# EFNMR_RT_V1.net
KiCad netlist of a schematic drawn in Altium Designer
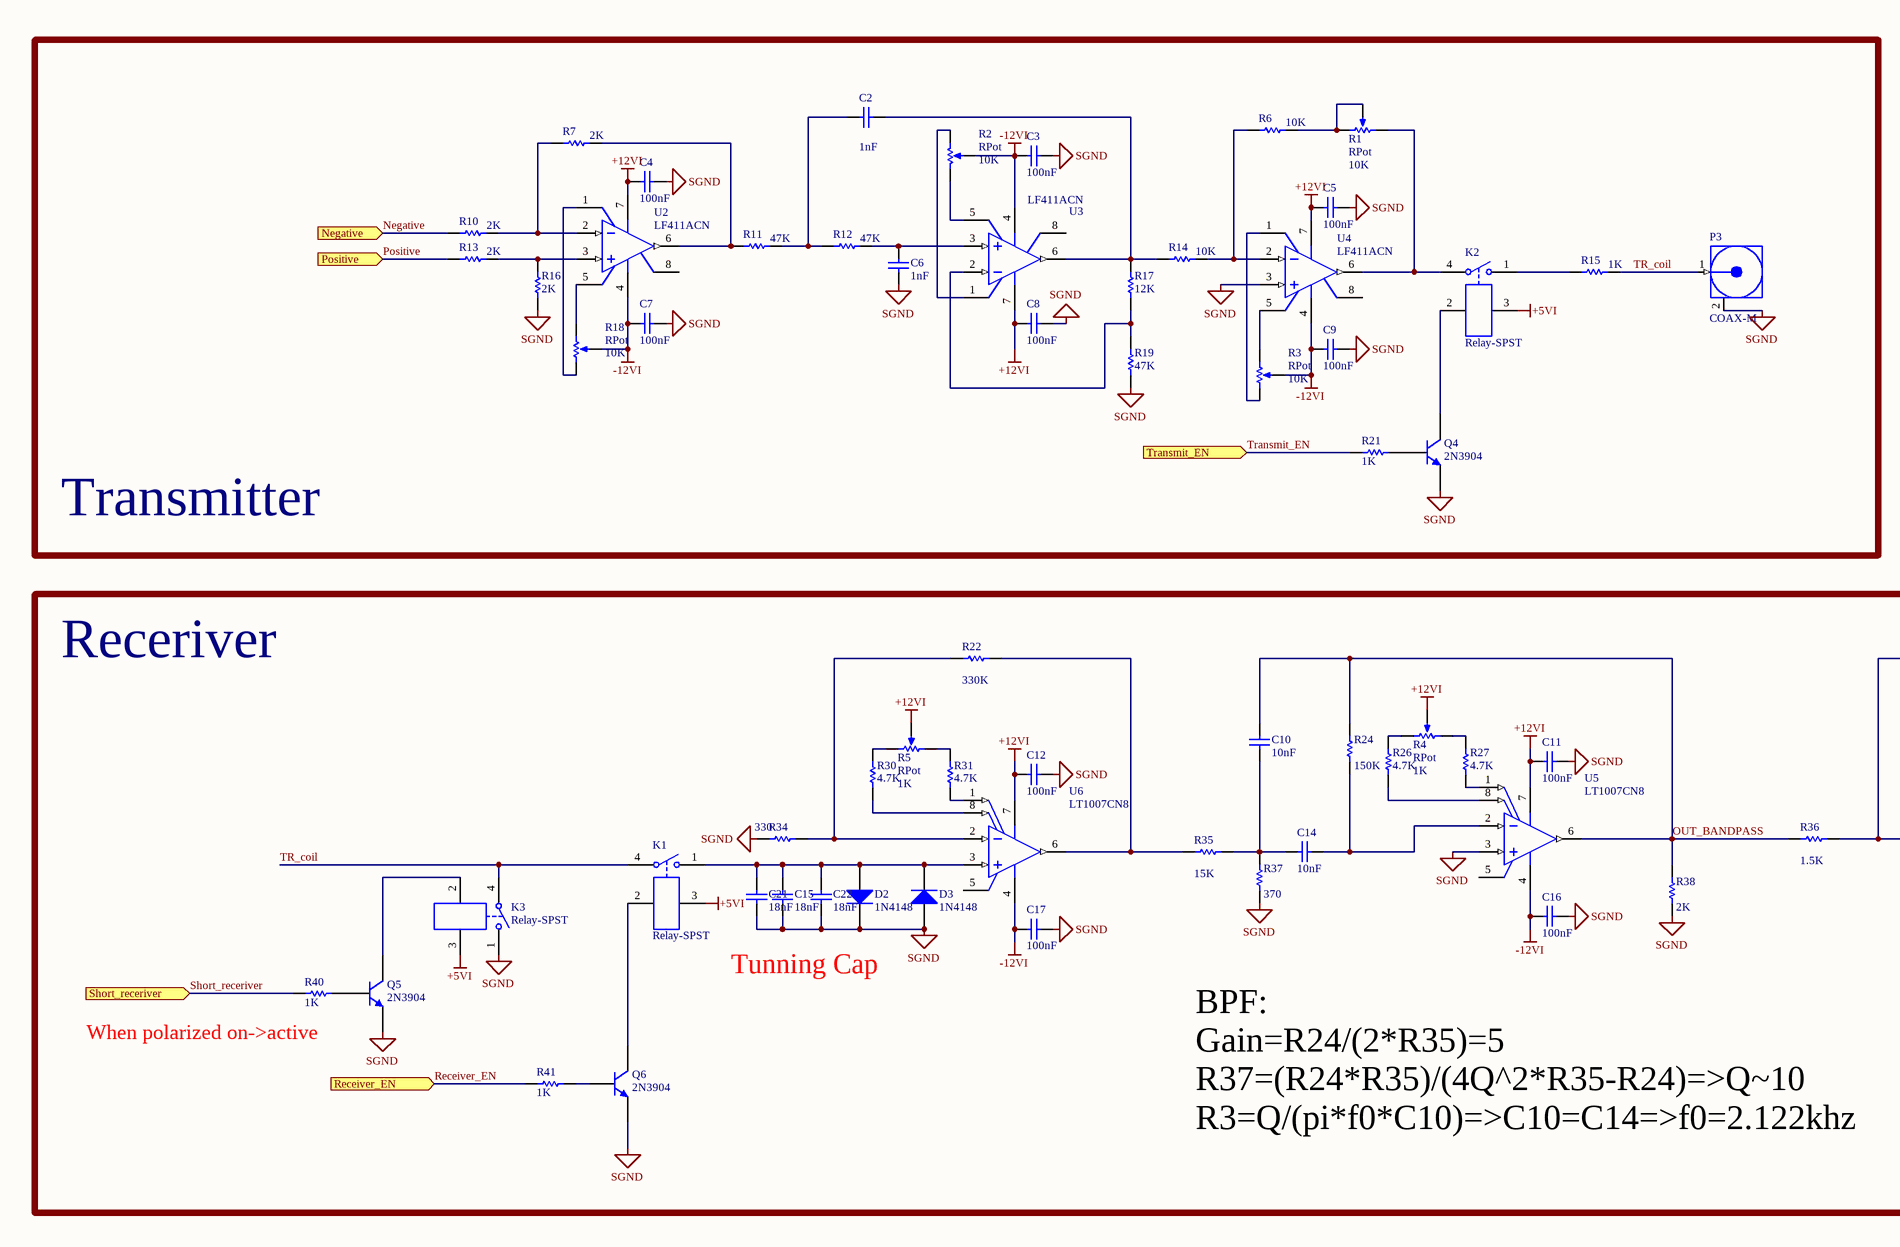
[diagram p0: EFNMR_RT_V1.SchDoc, left]
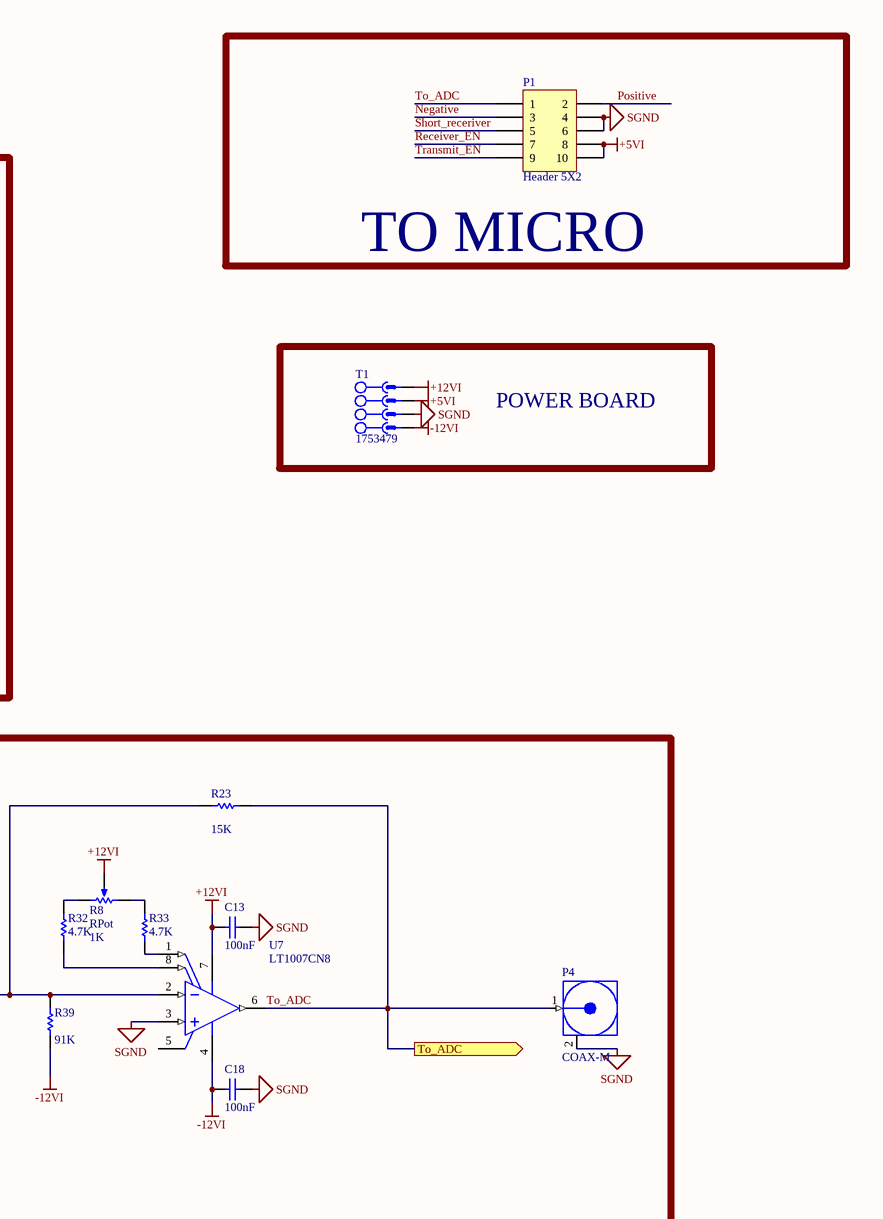
[diagram p1: EFNMR_RT_V1.SchDoc, right]

(export (version "E")
  (design (tool "Eeschema 10.0.6"))
  (components
    (comp (ref "C2")
      (value "1nF")
      (footprint "CAP0805")
      (description "Capacitor")
      (fields (field (name "Comment") "Cap") (field (name "PUBLISHER") "Altium Limited"))
      (libsource (lib "Miscellaneous Devices") (part "Cap"))
    )
    (comp (ref "C3")
      (value "100nF")
      (footprint "CAP0805")
      (description "Capacitor")
      (fields (field (name "Comment") "Cap") (field (name "PUBLISHER") "Altium Limited"))
      (libsource (lib "Miscellaneous Devices") (part "Cap"))
    )
    (comp (ref "C4")
      (value "100nF")
      (footprint "CAP0805")
      (description "Capacitor")
      (fields (field (name "Comment") "Cap") (field (name "PUBLISHER") "Altium Limited"))
      (libsource (lib "Miscellaneous Devices") (part "Cap"))
    )
    (comp (ref "C5")
      (value "100nF")
      (footprint "CAP0805")
      (description "Capacitor")
      (fields (field (name "Comment") "Cap") (field (name "PUBLISHER") "Altium Limited"))
      (libsource (lib "Miscellaneous Devices") (part "Cap"))
    )
    (comp (ref "C6")
      (value "1nF")
      (footprint "CAP0805")
      (description "Capacitor")
      (fields (field (name "Comment") "Cap") (field (name "PUBLISHER") "Altium Limited"))
      (libsource (lib "Miscellaneous Devices") (part "Cap"))
    )
    (comp (ref "C7")
      (value "100nF")
      (footprint "CAP0805")
      (description "Capacitor")
      (fields (field (name "Comment") "Cap") (field (name "PUBLISHER") "Altium Limited"))
      (libsource (lib "Miscellaneous Devices") (part "Cap"))
    )
    (comp (ref "C8")
      (value "100nF")
      (footprint "CAP0805")
      (description "Capacitor")
      (fields (field (name "Comment") "Cap") (field (name "PUBLISHER") "Altium Limited"))
      (libsource (lib "Miscellaneous Devices") (part "Cap"))
    )
    (comp (ref "C9")
      (value "100nF")
      (footprint "CAP0805")
      (description "Capacitor")
      (fields (field (name "Comment") "Cap") (field (name "PUBLISHER") "Altium Limited"))
      (libsource (lib "Miscellaneous Devices") (part "Cap"))
    )
    (comp (ref "C10")
      (value "10nF")
      (footprint "CAP0805")
      (description "Capacitor")
      (fields (field (name "PUBLISHER") "Altium Limited"))
      (libsource (lib "Miscellaneous Devices") (part "Cap"))
    )
    (comp (ref "C11")
      (value "100nF")
      (footprint "CAP0805")
      (description "Capacitor")
      (fields (field (name "Comment") "Cap") (field (name "PUBLISHER") "Altium Limited"))
      (libsource (lib "Miscellaneous Devices") (part "Cap"))
    )
    (comp (ref "C12")
      (value "100nF")
      (footprint "CAP0805")
      (description "Capacitor")
      (fields (field (name "Comment") "Cap") (field (name "PUBLISHER") "Altium Limited"))
      (libsource (lib "Miscellaneous Devices") (part "Cap"))
    )
    (comp (ref "C13")
      (value "100nF")
      (footprint "CAP0805")
      (description "Capacitor")
      (fields (field (name "Comment") "Cap") (field (name "PUBLISHER") "Altium Limited"))
      (libsource (lib "Miscellaneous Devices") (part "Cap"))
    )
    (comp (ref "C14")
      (value "10nF")
      (footprint "CAP0805")
      (description "Capacitor")
      (fields (field (name "PUBLISHER") "Altium Limited"))
      (libsource (lib "Miscellaneous Devices") (part "Cap"))
    )
    (comp (ref "C15")
      (value "18nF")
      (footprint "CAP0805")
      (description "Capacitor")
      (fields (field (name "Comment") "Cap") (field (name "PUBLISHER") "Altium Limited"))
      (libsource (lib "Miscellaneous Devices") (part "Cap"))
    )
    (comp (ref "C16")
      (value "100nF")
      (footprint "CAP0805")
      (description "Capacitor")
      (fields (field (name "Comment") "Cap") (field (name "PUBLISHER") "Altium Limited"))
      (libsource (lib "Miscellaneous Devices") (part "Cap"))
    )
    (comp (ref "C17")
      (value "100nF")
      (footprint "CAP0805")
      (description "Capacitor")
      (fields (field (name "Comment") "Cap") (field (name "PUBLISHER") "Altium Limited"))
      (libsource (lib "Miscellaneous Devices") (part "Cap"))
    )
    (comp (ref "C18")
      (value "100nF")
      (footprint "CAP0805")
      (description "Capacitor")
      (fields (field (name "Comment") "Cap") (field (name "PUBLISHER") "Altium Limited"))
      (libsource (lib "Miscellaneous Devices") (part "Cap"))
    )
    (comp (ref "C21")
      (value "18nF")
      (footprint "CAP0805")
      (description "Capacitor")
      (fields (field (name "Comment") "Cap") (field (name "PUBLISHER") "Altium Limited"))
      (libsource (lib "Miscellaneous Devices") (part "Cap"))
    )
    (comp (ref "C22")
      (value "18nF")
      (footprint "CAP0805")
      (description "Capacitor")
      (fields (field (name "Comment") "Cap") (field (name "PUBLISHER") "Altium Limited"))
      (libsource (lib "Miscellaneous Devices") (part "Cap"))
    )
    (comp (ref "D2")
      (value "1N4148")
      (footprint "SOD80, LL-34")
      (description "High Conductance Fast Diode")
      (fields (field (name "PUBLISHER") "Altium Limited"))
      (libsource (lib "FSC Discrete Diode") (part "1N4148"))
    )
    (comp (ref "D3")
      (value "1N4148")
      (footprint "SOD80, LL-34")
      (description "High Conductance Fast Diode")
      (fields (field (name "PUBLISHER") "Altium Limited"))
      (libsource (lib "FSC Discrete Diode") (part "1N4148"))
    )
    (comp (ref "K1")
      (value "Relay-SPST")
      (footprint "HE3351A0500")
      (description "Single-Pole Single-Throw Relay")
      (fields (field (name "PUBLISHER") "Altium Limited"))
      (libsource (lib "Miscellaneous Devices") (part "Relay-SPST"))
    )
    (comp (ref "K2")
      (value "Relay-SPST")
      (footprint "HE3351A0500")
      (description "Single-Pole Single-Throw Relay")
      (fields (field (name "PUBLISHER") "Altium Limited"))
      (libsource (lib "Miscellaneous Devices") (part "Relay-SPST"))
    )
    (comp (ref "K3")
      (value "Relay-SPST")
      (footprint "HE3351A0500")
      (description "Single-Pole Single-Throw Relay")
      (fields (field (name "PUBLISHER") "Altium Limited"))
      (libsource (lib "Miscellaneous Devices") (part "Relay-SPST"))
    )
    (comp (ref "P1")
      (value "Header 5X2")
      (footprint "IDC2.54-10PIN WITH CABLE")
      (description "Header, 5-Pin, Dual row")
      (fields (field (name "PUBLISHER") "Altium Limited"))
      (libsource (lib "Miscellaneous Connectors") (part "Header 5X2"))
    )
    (comp (ref "P3")
      (value "COAX-M")
      (footprint "SMA_RA_F")
      (description "RF Coaxial PCB Connector, MMCX; Thru-Hole, Vertical Mount Plug,  50 Ohm Impedance")
      (fields (field (name "PUBLISHER") "Altium Limited"))
      (libsource (lib "Miscellaneous Connectors") (part "COAX-M"))
    )
    (comp (ref "P4")
      (value "COAX-M")
      (footprint "SMA_RA_F")
      (description "RF Coaxial PCB Connector, MMCX; Thru-Hole, Vertical Mount Plug,  50 Ohm Impedance")
      (fields (field (name "PUBLISHER") "Altium Limited"))
      (libsource (lib "Miscellaneous Connectors") (part "COAX-M"))
    )
    (comp (ref "Q4")
      (value "2N3904")
      (footprint "TO-92A")
      (description "NPN General Purpose Amplifier")
      (fields (field (name "PUBLISHER") "Altium Limited"))
      (libsource (lib "Miscellaneous Devices") (part "2N3904"))
    )
    (comp (ref "Q5")
      (value "2N3904")
      (footprint "TO-92A")
      (description "NPN General Purpose Amplifier")
      (fields (field (name "PUBLISHER") "Altium Limited"))
      (libsource (lib "Miscellaneous Devices") (part "2N3904"))
    )
    (comp (ref "Q6")
      (value "2N3904")
      (footprint "TO-92A")
      (description "NPN General Purpose Amplifier")
      (fields (field (name "PUBLISHER") "Altium Limited"))
      (libsource (lib "Miscellaneous Devices") (part "2N3904"))
    )
    (comp (ref "R1")
      (value "RPot")
      (footprint "MULTITURN_TRIMMER_3296_132")
      (description "Potentiometer")
      (fields (field (name "ALTIUM_VALUE") "10K") (field (name "PUBLISHER") "Altium Limited"))
      (libsource (lib "Miscellaneous Devices") (part "RPot"))
    )
    (comp (ref "R2")
      (value "RPot")
      (footprint "MULTITURN_TRIMMER_3296_132")
      (description "Potentiometer")
      (fields (field (name "ALTIUM_VALUE") "10K") (field (name "PUBLISHER") "Altium Limited"))
      (libsource (lib "Miscellaneous Devices") (part "RPot"))
    )
    (comp (ref "R3")
      (value "RPot")
      (footprint "MULTITURN_TRIMMER_3296_132")
      (description "Potentiometer")
      (fields (field (name "ALTIUM_VALUE") "10K") (field (name "PUBLISHER") "Altium Limited"))
      (libsource (lib "Miscellaneous Devices") (part "RPot"))
    )
    (comp (ref "R4")
      (value "RPot")
      (footprint "MULTITURN_TRIMMER_3296_132")
      (description "Potentiometer")
      (fields (field (name "ALTIUM_VALUE") "1K") (field (name "PUBLISHER") "Altium Limited"))
      (libsource (lib "Miscellaneous Devices") (part "RPot"))
    )
    (comp (ref "R5")
      (value "RPot")
      (footprint "MULTITURN_TRIMMER_3296_132")
      (description "Potentiometer")
      (fields (field (name "ALTIUM_VALUE") "1K") (field (name "PUBLISHER") "Altium Limited"))
      (libsource (lib "Miscellaneous Devices") (part "RPot"))
    )
    (comp (ref "R6")
      (value "10K")
      (footprint "RES0805")
      (description "Resistor")
      (fields (field (name "PUBLISHER") "Altium Limited"))
      (libsource (lib "Miscellaneous Devices") (part "Res1"))
    )
    (comp (ref "R7")
      (value "2K")
      (footprint "RES0805")
      (description "Resistor")
      (fields (field (name "PUBLISHER") "Altium Limited"))
      (libsource (lib "Miscellaneous Devices") (part "Res1"))
    )
    (comp (ref "R8")
      (value "RPot")
      (footprint "MULTITURN_TRIMMER_3296_132")
      (description "Potentiometer")
      (fields (field (name "ALTIUM_VALUE") "1K") (field (name "PUBLISHER") "Altium Limited"))
      (libsource (lib "Miscellaneous Devices") (part "RPot"))
    )
    (comp (ref "R10")
      (value "2K")
      (footprint "RES0805")
      (description "Resistor")
      (fields (field (name "PUBLISHER") "Altium Limited"))
      (libsource (lib "Miscellaneous Devices") (part "Res1"))
    )
    (comp (ref "R11")
      (value "47K")
      (footprint "RES0805")
      (description "Resistor")
      (fields (field (name "PUBLISHER") "Altium Limited"))
      (libsource (lib "Miscellaneous Devices") (part "Res1"))
    )
    (comp (ref "R12")
      (value "47K")
      (footprint "RES0805")
      (description "Resistor")
      (fields (field (name "PUBLISHER") "Altium Limited"))
      (libsource (lib "Miscellaneous Devices") (part "Res1"))
    )
    (comp (ref "R13")
      (value "2K")
      (footprint "RES0805")
      (description "Resistor")
      (fields (field (name "PUBLISHER") "Altium Limited"))
      (libsource (lib "Miscellaneous Devices") (part "Res1"))
    )
    (comp (ref "R14")
      (value "10K")
      (footprint "RES0805")
      (description "Resistor")
      (fields (field (name "PUBLISHER") "Altium Limited"))
      (libsource (lib "Miscellaneous Devices") (part "Res1"))
    )
    (comp (ref "R15")
      (value "1K")
      (footprint "RES0805")
      (description "Resistor")
      (fields (field (name "PUBLISHER") "Altium Limited"))
      (libsource (lib "Miscellaneous Devices") (part "Res1"))
    )
    (comp (ref "R16")
      (value "2K")
      (footprint "RES0805")
      (description "Resistor")
      (fields (field (name "PUBLISHER") "Altium Limited"))
      (libsource (lib "Miscellaneous Devices") (part "Res1"))
    )
    (comp (ref "R17")
      (value "12K")
      (footprint "RES0805")
      (description "Resistor")
      (fields (field (name "PUBLISHER") "Altium Limited"))
      (libsource (lib "Miscellaneous Devices") (part "Res1"))
    )
    (comp (ref "R18")
      (value "RPot")
      (footprint "MULTITURN_TRIMMER_3296_132")
      (description "Potentiometer")
      (fields (field (name "ALTIUM_VALUE") "10K") (field (name "PUBLISHER") "Altium Limited"))
      (libsource (lib "Miscellaneous Devices") (part "RPot"))
    )
    (comp (ref "R19")
      (value "47K")
      (footprint "RES0805")
      (description "Resistor")
      (fields (field (name "PUBLISHER") "Altium Limited"))
      (libsource (lib "Miscellaneous Devices") (part "Res1"))
    )
    (comp (ref "R21")
      (value "1K")
      (footprint "RES0805")
      (description "Resistor")
      (fields (field (name "PUBLISHER") "Altium Limited"))
      (libsource (lib "Miscellaneous Devices") (part "Res1"))
    )
    (comp (ref "R22")
      (value "330K")
      (footprint "RES0805")
      (description "Resistor")
      (fields (field (name "PUBLISHER") "Altium Limited"))
      (libsource (lib "Miscellaneous Devices") (part "Res1"))
    )
    (comp (ref "R23")
      (value "15K")
      (footprint "RES0805")
      (description "Resistor")
      (fields (field (name "PUBLISHER") "Altium Limited"))
      (libsource (lib "Miscellaneous Devices") (part "Res1"))
    )
    (comp (ref "R24")
      (value "150K")
      (footprint "RES0805")
      (description "Resistor")
      (fields (field (name "PUBLISHER") "Altium Limited"))
      (libsource (lib "Miscellaneous Devices") (part "Res1"))
    )
    (comp (ref "R26")
      (value "4.7K")
      (footprint "RES0805")
      (description "Resistor")
      (fields (field (name "PUBLISHER") "Altium Limited"))
      (libsource (lib "Miscellaneous Devices") (part "Res1"))
    )
    (comp (ref "R27")
      (value "4.7K")
      (footprint "RES0805")
      (description "Resistor")
      (fields (field (name "PUBLISHER") "Altium Limited"))
      (libsource (lib "Miscellaneous Devices") (part "Res1"))
    )
    (comp (ref "R30")
      (value "4.7K")
      (footprint "RES0805")
      (description "Resistor")
      (fields (field (name "PUBLISHER") "Altium Limited"))
      (libsource (lib "Miscellaneous Devices") (part "Res1"))
    )
    (comp (ref "R31")
      (value "4.7K")
      (footprint "RES0805")
      (description "Resistor")
      (fields (field (name "PUBLISHER") "Altium Limited"))
      (libsource (lib "Miscellaneous Devices") (part "Res1"))
    )
    (comp (ref "R32")
      (value "4.7K")
      (footprint "RES0805")
      (description "Resistor")
      (fields (field (name "PUBLISHER") "Altium Limited"))
      (libsource (lib "Miscellaneous Devices") (part "Res1"))
    )
    (comp (ref "R33")
      (value "4.7K")
      (footprint "RES0805")
      (description "Resistor")
      (fields (field (name "PUBLISHER") "Altium Limited"))
      (libsource (lib "Miscellaneous Devices") (part "Res1"))
    )
    (comp (ref "R34")
      (value "330")
      (footprint "RES0805")
      (description "Resistor")
      (fields (field (name "PUBLISHER") "Altium Limited"))
      (libsource (lib "Miscellaneous Devices") (part "Res1"))
    )
    (comp (ref "R35")
      (value "15K")
      (footprint "RES0805")
      (description "Resistor")
      (fields (field (name "PUBLISHER") "Altium Limited"))
      (libsource (lib "Miscellaneous Devices") (part "Res1"))
    )
    (comp (ref "R36")
      (value "1.5K")
      (footprint "RES0805")
      (description "Resistor")
      (fields (field (name "PUBLISHER") "Altium Limited"))
      (libsource (lib "Miscellaneous Devices") (part "Res1"))
    )
    (comp (ref "R37")
      (value "370")
      (footprint "RES0805")
      (description "Resistor")
      (fields (field (name "PUBLISHER") "Altium Limited"))
      (libsource (lib "Miscellaneous Devices") (part "Res1"))
    )
    (comp (ref "R38")
      (value "2K")
      (footprint "RES0805")
      (description "Resistor")
      (fields (field (name "PUBLISHER") "Altium Limited"))
      (libsource (lib "Miscellaneous Devices") (part "Res1"))
    )
    (comp (ref "R39")
      (value "91K")
      (footprint "RES0805")
      (description "Resistor")
      (fields (field (name "PUBLISHER") "Altium Limited"))
      (libsource (lib "Miscellaneous Devices") (part "Res1"))
    )
    (comp (ref "R40")
      (value "1K")
      (footprint "RES0805")
      (description "Resistor")
      (fields (field (name "PUBLISHER") "Altium Limited"))
      (libsource (lib "Miscellaneous Devices") (part "Res1"))
    )
    (comp (ref "R41")
      (value "1K")
      (footprint "RES0805")
      (description "Resistor")
      (fields (field (name "PUBLISHER") "Altium Limited"))
      (libsource (lib "Miscellaneous Devices") (part "Res1"))
    )
    (comp (ref "T1")
      (value "1753479")
      (footprint "MSTBV 2,5/4-G-5")
      (description "4 Pitch: 5 mm Color: green Contact surface: Tin Assembly")
      (fields
        (field (name "MANUFACTURER") "PHOENIX CONTACT")
        (field (name "VOLTAGE") "320 V")
        (field (name "DESIGNER") "ABBAS BASEREH")
      )
      (libsource (lib "Mofidi3D") (part "CON_Phoenix_MSTBV_04"))
    )
    (comp (ref "U2")
      (value "LF411ACN")
      (footprint "LT-N8-8")
      (description "Low Offset, Low Drift JFET Input Operational Amplifier, 8-pin MDIP")
      (fields (field (name "MANUFACTURER") "National Semiconductor"))
      (libsource (lib "National Semiconductor Amplifier") (part "LF411ACN"))
    )
    (comp (ref "U3")
      (value "LF411ACN")
      (footprint "LT-N8-8")
      (description "Low Offset, Low Drift JFET Input Operational Amplifier, 8-pin MDIP")
      (fields (field (name "MANUFACTURER") "National Semiconductor"))
      (libsource (lib "National Semiconductor Amplifier") (part "LF411ACN"))
    )
    (comp (ref "U4")
      (value "LF411ACN")
      (footprint "LT-N8-8")
      (description "Low Offset, Low Drift JFET Input Operational Amplifier, 8-pin MDIP")
      (fields (field (name "MANUFACTURER") "National Semiconductor"))
      (libsource (lib "National Semiconductor Amplifier") (part "LF411ACN"))
    )
    (comp (ref "U5")
      (value "LT1007CN8")
      (footprint "LT-N8-8")
      (fields
        (field (name "LINEAR TECHNOLOGY PART NUMBER") "LT1007")
        (field (name "MANUFACTURER") "Linear Technology")
      )
      (libsource (lib "Linear Technology Operational Amplifiers (LT1000)") (part "LT1007CN8"))
    )
    (comp (ref "U6")
      (value "LT1007CN8")
      (footprint "LT-N8-8")
      (fields
        (field (name "LINEAR TECHNOLOGY PART NUMBER") "LT1007")
        (field (name "MANUFACTURER") "Linear Technology")
      )
      (libsource (lib "Linear Technology Operational Amplifiers (LT1000)") (part "LT1007CN8"))
    )
    (comp (ref "U7")
      (value "LT1007CN8")
      (footprint "LT-N8-8")
      (fields
        (field (name "LINEAR TECHNOLOGY PART NUMBER") "LT1007")
        (field (name "MANUFACTURER") "Linear Technology")
      )
      (libsource (lib "Linear Technology Operational Amplifiers (LT1000)") (part "LT1007CN8"))
    )
  )
  (nets
    (net (code "1") (name "+5VI") (class "Default")
      (node (ref "K1") (pin "3") (pinfunction "3_3") (pintype "passive"))
      (node (ref "K2") (pin "3") (pinfunction "3_3") (pintype "passive"))
      (node (ref "K3") (pin "3") (pinfunction "3_3") (pintype "passive"))
      (node (ref "P1") (pin "10") (pinfunction "10_10") (pintype "passive"))
      (node (ref "P1") (pin "8") (pinfunction "8_8") (pintype "passive"))
      (node (ref "T1") (pin "3") (pinfunction "3_3") (pintype "passive"))
    )
    (net (code "2") (name "+12VI") (class "Default")
      (node (ref "C11") (pin "2") (pinfunction "2_2") (pintype "passive"))
      (node (ref "C12") (pin "2") (pinfunction "2_2") (pintype "passive"))
      (node (ref "C13") (pin "2") (pinfunction "2_2") (pintype "passive"))
      (node (ref "C4") (pin "2") (pinfunction "2_2") (pintype "passive"))
      (node (ref "C5") (pin "2") (pinfunction "2_2") (pintype "passive"))
      (node (ref "C8") (pin "2") (pinfunction "2_2") (pintype "passive"))
      (node (ref "R4") (pin "3") (pinfunction "TAP_3") (pintype "passive"))
      (node (ref "R5") (pin "3") (pinfunction "TAP_3") (pintype "passive"))
      (node (ref "R8") (pin "3") (pinfunction "TAP_3") (pintype "passive"))
      (node (ref "T1") (pin "4") (pinfunction "4_4") (pintype "passive"))
      (node (ref "U2") (pin "7") (pinfunction "V+_7") (pintype "power_in"))
      (node (ref "U3") (pin "7") (pinfunction "V+_7") (pintype "power_in"))
      (node (ref "U4") (pin "7") (pinfunction "V+_7") (pintype "power_in"))
      (node (ref "U5") (pin "7") (pinfunction "V+_7") (pintype "power_in"))
      (node (ref "U6") (pin "7") (pinfunction "V+_7") (pintype "power_in"))
      (node (ref "U7") (pin "7") (pinfunction "V+_7") (pintype "power_in"))
    )
    (net (code "3") (name "-12VI") (class "Default")
      (node (ref "C16") (pin "2") (pinfunction "2_2") (pintype "passive"))
      (node (ref "C17") (pin "2") (pinfunction "2_2") (pintype "passive"))
      (node (ref "C18") (pin "2") (pinfunction "2_2") (pintype "passive"))
      (node (ref "C3") (pin "2") (pinfunction "2_2") (pintype "passive"))
      (node (ref "C7") (pin "2") (pinfunction "2_2") (pintype "passive"))
      (node (ref "C9") (pin "2") (pinfunction "2_2") (pintype "passive"))
      (node (ref "R18") (pin "3") (pinfunction "TAP_3") (pintype "passive"))
      (node (ref "R2") (pin "3") (pinfunction "TAP_3") (pintype "passive"))
      (node (ref "R3") (pin "3") (pinfunction "TAP_3") (pintype "passive"))
      (node (ref "R39") (pin "2") (pinfunction "2_2") (pintype "passive"))
      (node (ref "T1") (pin "1") (pinfunction "1_1") (pintype "passive"))
      (node (ref "U2") (pin "4") (pinfunction "V-_4") (pintype "power_in"))
      (node (ref "U3") (pin "4") (pinfunction "V-_4") (pintype "power_in"))
      (node (ref "U4") (pin "4") (pinfunction "V-_4") (pintype "power_in"))
      (node (ref "U5") (pin "4") (pinfunction "V-_4") (pintype "power_in"))
      (node (ref "U6") (pin "4") (pinfunction "V-_4") (pintype "power_in"))
      (node (ref "U7") (pin "4") (pinfunction "V-_4") (pintype "power_in"))
    )
    (net (code "4") (name "/Negative") (class "Default")
      (node (ref "P1") (pin "3") (pinfunction "3_3") (pintype "passive"))
      (node (ref "R10") (pin "1") (pinfunction "1_1") (pintype "passive"))
    )
    (net (code "5") (name "/OUT_BANDPASS") (class "Default")
      (node (ref "C10") (pin "2") (pinfunction "2_2") (pintype "passive"))
      (node (ref "R24") (pin "1") (pinfunction "1_1") (pintype "passive"))
      (node (ref "R36") (pin "2") (pinfunction "2_2") (pintype "passive"))
      (node (ref "R38") (pin "1") (pinfunction "1_1") (pintype "passive"))
      (node (ref "U5") (pin "6") (pinfunction "OUT_6") (pintype "output"))
    )
    (net (code "6") (name "/Positive") (class "Default")
      (node (ref "P1") (pin "2") (pinfunction "2_2") (pintype "passive"))
      (node (ref "R13") (pin "1") (pinfunction "1_1") (pintype "passive"))
    )
    (net (code "7") (name "/Receiver_EN") (class "Default")
      (node (ref "P1") (pin "7") (pinfunction "7_7") (pintype "passive"))
      (node (ref "R41") (pin "2") (pinfunction "2_2") (pintype "passive"))
    )
    (net (code "8") (name "/Short_receriver") (class "Default")
      (node (ref "P1") (pin "5") (pinfunction "5_5") (pintype "passive"))
      (node (ref "R40") (pin "2") (pinfunction "2_2") (pintype "passive"))
    )
    (net (code "9") (name "/TR_coil") (class "Default")
      (node (ref "K1") (pin "4") (pinfunction "4_4") (pintype "passive"))
      (node (ref "K3") (pin "4") (pinfunction "4_4") (pintype "passive"))
      (node (ref "P3") (pin "1") (pinfunction "Signal_1") (pintype "input"))
      (node (ref "R15") (pin "2") (pinfunction "2_2") (pintype "passive"))
    )
    (net (code "10") (name "/To_ADC") (class "Default")
      (node (ref "P1") (pin "1") (pinfunction "1_1") (pintype "passive"))
      (node (ref "P4") (pin "1") (pinfunction "Signal_1") (pintype "input"))
      (node (ref "R23") (pin "1") (pinfunction "1_1") (pintype "passive"))
      (node (ref "U7") (pin "6") (pinfunction "OUT_6") (pintype "output"))
    )
    (net (code "11") (name "/Transmit_EN") (class "Default")
      (node (ref "P1") (pin "9") (pinfunction "9_9") (pintype "passive"))
      (node (ref "R21") (pin "2") (pinfunction "2_2") (pintype "passive"))
    )
    (net (code "12") (name "Net-(C2-Pad1)") (class "Default")
      (node (ref "C2") (pin "1") (pinfunction "1_1") (pintype "passive"))
      (node (ref "R11") (pin "2") (pinfunction "2_2") (pintype "passive"))
      (node (ref "R12") (pin "1") (pinfunction "1_1") (pintype "passive"))
    )
    (net (code "13") (name "Net-(C10-Pad1)") (class "Default")
      (node (ref "C10") (pin "1") (pinfunction "1_1") (pintype "passive"))
      (node (ref "C14") (pin "1") (pinfunction "1_1") (pintype "passive"))
      (node (ref "R35") (pin "1") (pinfunction "1_1") (pintype "passive"))
      (node (ref "R37") (pin "1") (pinfunction "1_1") (pintype "passive"))
    )
    (net (code "14") (name "Net-(D2-A)") (class "Default")
      (node (ref "C15") (pin "1") (pinfunction "1_1") (pintype "passive"))
      (node (ref "C21") (pin "1") (pinfunction "1_1") (pintype "passive"))
      (node (ref "C22") (pin "1") (pinfunction "1_1") (pintype "passive"))
      (node (ref "D2") (pin "1") (pinfunction "A_1") (pintype "passive"))
      (node (ref "D3") (pin "2") (pinfunction "K_2") (pintype "passive"))
      (node (ref "K1") (pin "1") (pinfunction "1_1") (pintype "passive"))
      (node (ref "U6") (pin "3") (pinfunction "+IN_3") (pintype "input"))
    )
    (net (code "15") (name "Net-(K2-Pad1)") (class "Default")
      (node (ref "K2") (pin "1") (pinfunction "1_1") (pintype "passive"))
      (node (ref "R15") (pin "1") (pinfunction "1_1") (pintype "passive"))
    )
    (net (code "16") (name "Net-(Q4-B)") (class "Default")
      (node (ref "Q4") (pin "2") (pinfunction "B_2") (pintype "passive"))
      (node (ref "R21") (pin "1") (pinfunction "1_1") (pintype "passive"))
    )
    (net (code "17") (name "Net-(Q4-C)") (class "Default")
      (node (ref "K2") (pin "2") (pinfunction "2_2") (pintype "passive"))
      (node (ref "Q4") (pin "3") (pinfunction "C_3") (pintype "passive"))
    )
    (net (code "18") (name "Net-(Q5-B)") (class "Default")
      (node (ref "Q5") (pin "2") (pinfunction "B_2") (pintype "passive"))
      (node (ref "R40") (pin "1") (pinfunction "1_1") (pintype "passive"))
    )
    (net (code "19") (name "Net-(Q5-C)") (class "Default")
      (node (ref "K3") (pin "2") (pinfunction "2_2") (pintype "passive"))
      (node (ref "Q5") (pin "3") (pinfunction "C_3") (pintype "passive"))
    )
    (net (code "20") (name "Net-(Q6-B)") (class "Default")
      (node (ref "Q6") (pin "2") (pinfunction "B_2") (pintype "passive"))
      (node (ref "R41") (pin "1") (pinfunction "1_1") (pintype "passive"))
    )
    (net (code "21") (name "Net-(Q6-C)") (class "Default")
      (node (ref "K1") (pin "2") (pinfunction "2_2") (pintype "passive"))
      (node (ref "Q6") (pin "3") (pinfunction "C_3") (pintype "passive"))
    )
    (net (code "22") (name "Net-(R1-BOT)") (class "Default")
      (node (ref "R1") (pin "2") (pinfunction "BOT_2") (pintype "passive"))
      (node (ref "R1") (pin "3") (pinfunction "TAP_3") (pintype "passive"))
      (node (ref "R6") (pin "2") (pinfunction "2_2") (pintype "passive"))
    )
    (net (code "23") (name "Net-(R1-TOP)") (class "Default")
      (node (ref "K2") (pin "4") (pinfunction "4_4") (pintype "passive"))
      (node (ref "R1") (pin "1") (pinfunction "TOP_1") (pintype "passive"))
      (node (ref "U4") (pin "6") (pinfunction "OUT_6") (pintype "output"))
    )
    (net (code "24") (name "Net-(R2-BOT)") (class "Default")
      (node (ref "R2") (pin "2") (pinfunction "BOT_2") (pintype "passive"))
      (node (ref "U3") (pin "5") (pinfunction "BAL_5") (pintype "passive"))
    )
    (net (code "25") (name "Net-(R2-TOP)") (class "Default")
      (node (ref "R2") (pin "1") (pinfunction "TOP_1") (pintype "passive"))
      (node (ref "U3") (pin "1") (pinfunction "BAL_1") (pintype "passive"))
    )
    (net (code "26") (name "Net-(R3-BOT)") (class "Default")
      (node (ref "R3") (pin "2") (pinfunction "BOT_2") (pintype "passive"))
      (node (ref "U4") (pin "5") (pinfunction "BAL_5") (pintype "passive"))
    )
    (net (code "27") (name "Net-(R3-TOP)") (class "Default")
      (node (ref "R3") (pin "1") (pinfunction "TOP_1") (pintype "passive"))
      (node (ref "U4") (pin "1") (pinfunction "BAL_1") (pintype "passive"))
    )
    (net (code "28") (name "Net-(R4-BOT)") (class "Default")
      (node (ref "R26") (pin "1") (pinfunction "1_1") (pintype "passive"))
      (node (ref "R4") (pin "2") (pinfunction "BOT_2") (pintype "passive"))
    )
    (net (code "29") (name "Net-(R4-TOP)") (class "Default")
      (node (ref "R27") (pin "1") (pinfunction "1_1") (pintype "passive"))
      (node (ref "R4") (pin "1") (pinfunction "TOP_1") (pintype "passive"))
    )
    (net (code "30") (name "Net-(R5-BOT)") (class "Default")
      (node (ref "R30") (pin "1") (pinfunction "1_1") (pintype "passive"))
      (node (ref "R5") (pin "2") (pinfunction "BOT_2") (pintype "passive"))
    )
    (net (code "31") (name "Net-(R5-TOP)") (class "Default")
      (node (ref "R31") (pin "1") (pinfunction "1_1") (pintype "passive"))
      (node (ref "R5") (pin "1") (pinfunction "TOP_1") (pintype "passive"))
    )
    (net (code "32") (name "Net-(R8-BOT)") (class "Default")
      (node (ref "R32") (pin "1") (pinfunction "1_1") (pintype "passive"))
      (node (ref "R8") (pin "2") (pinfunction "BOT_2") (pintype "passive"))
    )
    (net (code "33") (name "Net-(R8-TOP)") (class "Default")
      (node (ref "R33") (pin "1") (pinfunction "1_1") (pintype "passive"))
      (node (ref "R8") (pin "1") (pinfunction "TOP_1") (pintype "passive"))
    )
    (net (code "34") (name "Net-(R18-BOT)") (class "Default")
      (node (ref "R18") (pin "2") (pinfunction "BOT_2") (pintype "passive"))
      (node (ref "U2") (pin "5") (pinfunction "BAL_5") (pintype "passive"))
    )
    (net (code "35") (name "Net-(R18-TOP)") (class "Default")
      (node (ref "R18") (pin "1") (pinfunction "TOP_1") (pintype "passive"))
      (node (ref "U2") (pin "1") (pinfunction "BAL_1") (pintype "passive"))
    )
    (net (code "36") (name "Net-(R26-Pad2)") (class "Default")
      (node (ref "R26") (pin "2") (pinfunction "2_2") (pintype "passive"))
      (node (ref "U5") (pin "8") (pinfunction "VOS_TRIM_8") (pintype "input"))
    )
    (net (code "37") (name "Net-(R27-Pad2)") (class "Default")
      (node (ref "R27") (pin "2") (pinfunction "2_2") (pintype "passive"))
      (node (ref "U5") (pin "1") (pinfunction "VOS_TRIM_1") (pintype "input"))
    )
    (net (code "38") (name "Net-(R30-Pad2)") (class "Default")
      (node (ref "R30") (pin "2") (pinfunction "2_2") (pintype "passive"))
      (node (ref "U6") (pin "8") (pinfunction "VOS_TRIM_8") (pintype "input"))
    )
    (net (code "39") (name "Net-(R31-Pad2)") (class "Default")
      (node (ref "R31") (pin "2") (pinfunction "2_2") (pintype "passive"))
      (node (ref "U6") (pin "1") (pinfunction "VOS_TRIM_1") (pintype "input"))
    )
    (net (code "40") (name "Net-(R32-Pad2)") (class "Default")
      (node (ref "R32") (pin "2") (pinfunction "2_2") (pintype "passive"))
      (node (ref "U7") (pin "8") (pinfunction "VOS_TRIM_8") (pintype "input"))
    )
    (net (code "41") (name "Net-(R33-Pad2)") (class "Default")
      (node (ref "R33") (pin "2") (pinfunction "2_2") (pintype "passive"))
      (node (ref "U7") (pin "1") (pinfunction "VOS_TRIM_1") (pintype "input"))
    )
    (net (code "42") (name "Net-(U2-IN+)") (class "Default")
      (node (ref "R13") (pin "2") (pinfunction "2_2") (pintype "passive"))
      (node (ref "R16") (pin "2") (pinfunction "2_2") (pintype "passive"))
      (node (ref "U2") (pin "3") (pinfunction "IN+_3") (pintype "input"))
    )
    (net (code "43") (name "Net-(U2-IN-)") (class "Default")
      (node (ref "R10") (pin "2") (pinfunction "2_2") (pintype "passive"))
      (node (ref "R7") (pin "1") (pinfunction "1_1") (pintype "passive"))
      (node (ref "U2") (pin "2") (pinfunction "IN-_2") (pintype "input"))
    )
    (net (code "44") (name "Net-(U2-OUT)") (class "Default")
      (node (ref "R11") (pin "1") (pinfunction "1_1") (pintype "passive"))
      (node (ref "R7") (pin "2") (pinfunction "2_2") (pintype "passive"))
      (node (ref "U2") (pin "6") (pinfunction "OUT_6") (pintype "output"))
    )
    (net (code "45") (name "Net-(U3-IN+)") (class "Default")
      (node (ref "C6") (pin "2") (pinfunction "2_2") (pintype "passive"))
      (node (ref "R12") (pin "2") (pinfunction "2_2") (pintype "passive"))
      (node (ref "U3") (pin "3") (pinfunction "IN+_3") (pintype "input"))
    )
    (net (code "46") (name "Net-(U3-IN-)") (class "Default")
      (node (ref "R17") (pin "2") (pinfunction "2_2") (pintype "passive"))
      (node (ref "R19") (pin "2") (pinfunction "2_2") (pintype "passive"))
      (node (ref "U3") (pin "2") (pinfunction "IN-_2") (pintype "input"))
    )
    (net (code "47") (name "Net-(U3-OUT)") (class "Default")
      (node (ref "C2") (pin "2") (pinfunction "2_2") (pintype "passive"))
      (node (ref "R14") (pin "1") (pinfunction "1_1") (pintype "passive"))
      (node (ref "R17") (pin "1") (pinfunction "1_1") (pintype "passive"))
      (node (ref "U3") (pin "6") (pinfunction "OUT_6") (pintype "output"))
    )
    (net (code "48") (name "Net-(U4-IN-)") (class "Default")
      (node (ref "R14") (pin "2") (pinfunction "2_2") (pintype "passive"))
      (node (ref "R6") (pin "1") (pinfunction "1_1") (pintype "passive"))
      (node (ref "U4") (pin "2") (pinfunction "IN-_2") (pintype "input"))
    )
    (net (code "49") (name "Net-(U5--IN)") (class "Default")
      (node (ref "C14") (pin "2") (pinfunction "2_2") (pintype "passive"))
      (node (ref "R24") (pin "2") (pinfunction "2_2") (pintype "passive"))
      (node (ref "U5") (pin "2") (pinfunction "-IN_2") (pintype "input"))
    )
    (net (code "50") (name "Net-(U6--IN)") (class "Default")
      (node (ref "R22") (pin "2") (pinfunction "2_2") (pintype "passive"))
      (node (ref "R34") (pin "2") (pinfunction "2_2") (pintype "passive"))
      (node (ref "U6") (pin "2") (pinfunction "-IN_2") (pintype "input"))
    )
    (net (code "51") (name "Net-(U6-OUT)") (class "Default")
      (node (ref "R22") (pin "1") (pinfunction "1_1") (pintype "passive"))
      (node (ref "R35") (pin "2") (pinfunction "2_2") (pintype "passive"))
      (node (ref "U6") (pin "6") (pinfunction "OUT_6") (pintype "output"))
    )
    (net (code "52") (name "Net-(U7--IN)") (class "Default")
      (node (ref "R23") (pin "2") (pinfunction "2_2") (pintype "passive"))
      (node (ref "R36") (pin "1") (pinfunction "1_1") (pintype "passive"))
      (node (ref "R39") (pin "1") (pinfunction "1_1") (pintype "passive"))
      (node (ref "U7") (pin "2") (pinfunction "-IN_2") (pintype "input"))
    )
    (net (code "53") (name "SGND") (class "Default")
      (node (ref "C11") (pin "1") (pinfunction "1_1") (pintype "passive"))
      (node (ref "C12") (pin "1") (pinfunction "1_1") (pintype "passive"))
      (node (ref "C13") (pin "1") (pinfunction "1_1") (pintype "passive"))
      (node (ref "C15") (pin "2") (pinfunction "2_2") (pintype "passive"))
      (node (ref "C16") (pin "1") (pinfunction "1_1") (pintype "passive"))
      (node (ref "C17") (pin "1") (pinfunction "1_1") (pintype "passive"))
      (node (ref "C18") (pin "1") (pinfunction "1_1") (pintype "passive"))
      (node (ref "C21") (pin "2") (pinfunction "2_2") (pintype "passive"))
      (node (ref "C22") (pin "2") (pinfunction "2_2") (pintype "passive"))
      (node (ref "C3") (pin "1") (pinfunction "1_1") (pintype "passive"))
      (node (ref "C4") (pin "1") (pinfunction "1_1") (pintype "passive"))
      (node (ref "C5") (pin "1") (pinfunction "1_1") (pintype "passive"))
      (node (ref "C6") (pin "1") (pinfunction "1_1") (pintype "passive"))
      (node (ref "C7") (pin "1") (pinfunction "1_1") (pintype "passive"))
      (node (ref "C8") (pin "1") (pinfunction "1_1") (pintype "passive"))
      (node (ref "C9") (pin "1") (pinfunction "1_1") (pintype "passive"))
      (node (ref "D2") (pin "2") (pinfunction "K_2") (pintype "passive"))
      (node (ref "D3") (pin "1") (pinfunction "A_1") (pintype "passive"))
      (node (ref "K3") (pin "1") (pinfunction "1_1") (pintype "passive"))
      (node (ref "P1") (pin "4") (pinfunction "4_4") (pintype "passive"))
      (node (ref "P1") (pin "6") (pinfunction "6_6") (pintype "passive"))
      (node (ref "P3") (pin "2") (pinfunction "GND_2") (pintype "power_in"))
      (node (ref "P4") (pin "2") (pinfunction "GND_2") (pintype "power_in"))
      (node (ref "Q4") (pin "1") (pinfunction "E_1") (pintype "passive"))
      (node (ref "Q5") (pin "1") (pinfunction "E_1") (pintype "passive"))
      (node (ref "Q6") (pin "1") (pinfunction "E_1") (pintype "passive"))
      (node (ref "R16") (pin "1") (pinfunction "1_1") (pintype "passive"))
      (node (ref "R19") (pin "1") (pinfunction "1_1") (pintype "passive"))
      (node (ref "R34") (pin "1") (pinfunction "1_1") (pintype "passive"))
      (node (ref "R37") (pin "2") (pinfunction "2_2") (pintype "passive"))
      (node (ref "R38") (pin "2") (pinfunction "2_2") (pintype "passive"))
      (node (ref "T1") (pin "2") (pinfunction "2_2") (pintype "passive"))
      (node (ref "U4") (pin "3") (pinfunction "IN+_3") (pintype "input"))
      (node (ref "U5") (pin "3") (pinfunction "+IN_3") (pintype "input"))
      (node (ref "U7") (pin "3") (pinfunction "+IN_3") (pintype "input"))
    )
    (net (code "54") (name "unconnected-(U2-NC-Pad8)") (class "Default")
      (node (ref "U2") (pin "8") (pinfunction "NC_8") (pintype "passive"))
    )
    (net (code "55") (name "unconnected-(U3-NC-Pad8)") (class "Default")
      (node (ref "U3") (pin "8") (pinfunction "NC_8") (pintype "passive"))
    )
    (net (code "56") (name "unconnected-(U4-NC-Pad8)") (class "Default")
      (node (ref "U4") (pin "8") (pinfunction "NC_8") (pintype "passive"))
    )
    (net (code "57") (name "unconnected-(U5-NC-Pad5)") (class "Default")
      (node (ref "U5") (pin "5") (pinfunction "NC_5") (pintype "passive"))
    )
    (net (code "58") (name "unconnected-(U6-NC-Pad5)") (class "Default")
      (node (ref "U6") (pin "5") (pinfunction "NC_5") (pintype "passive"))
    )
    (net (code "59") (name "unconnected-(U7-NC-Pad5)") (class "Default")
      (node (ref "U7") (pin "5") (pinfunction "NC_5") (pintype "passive"))
    )
  )
)
